# AST2003.net
KiCad netlist of a schematic drawn in EAGLE
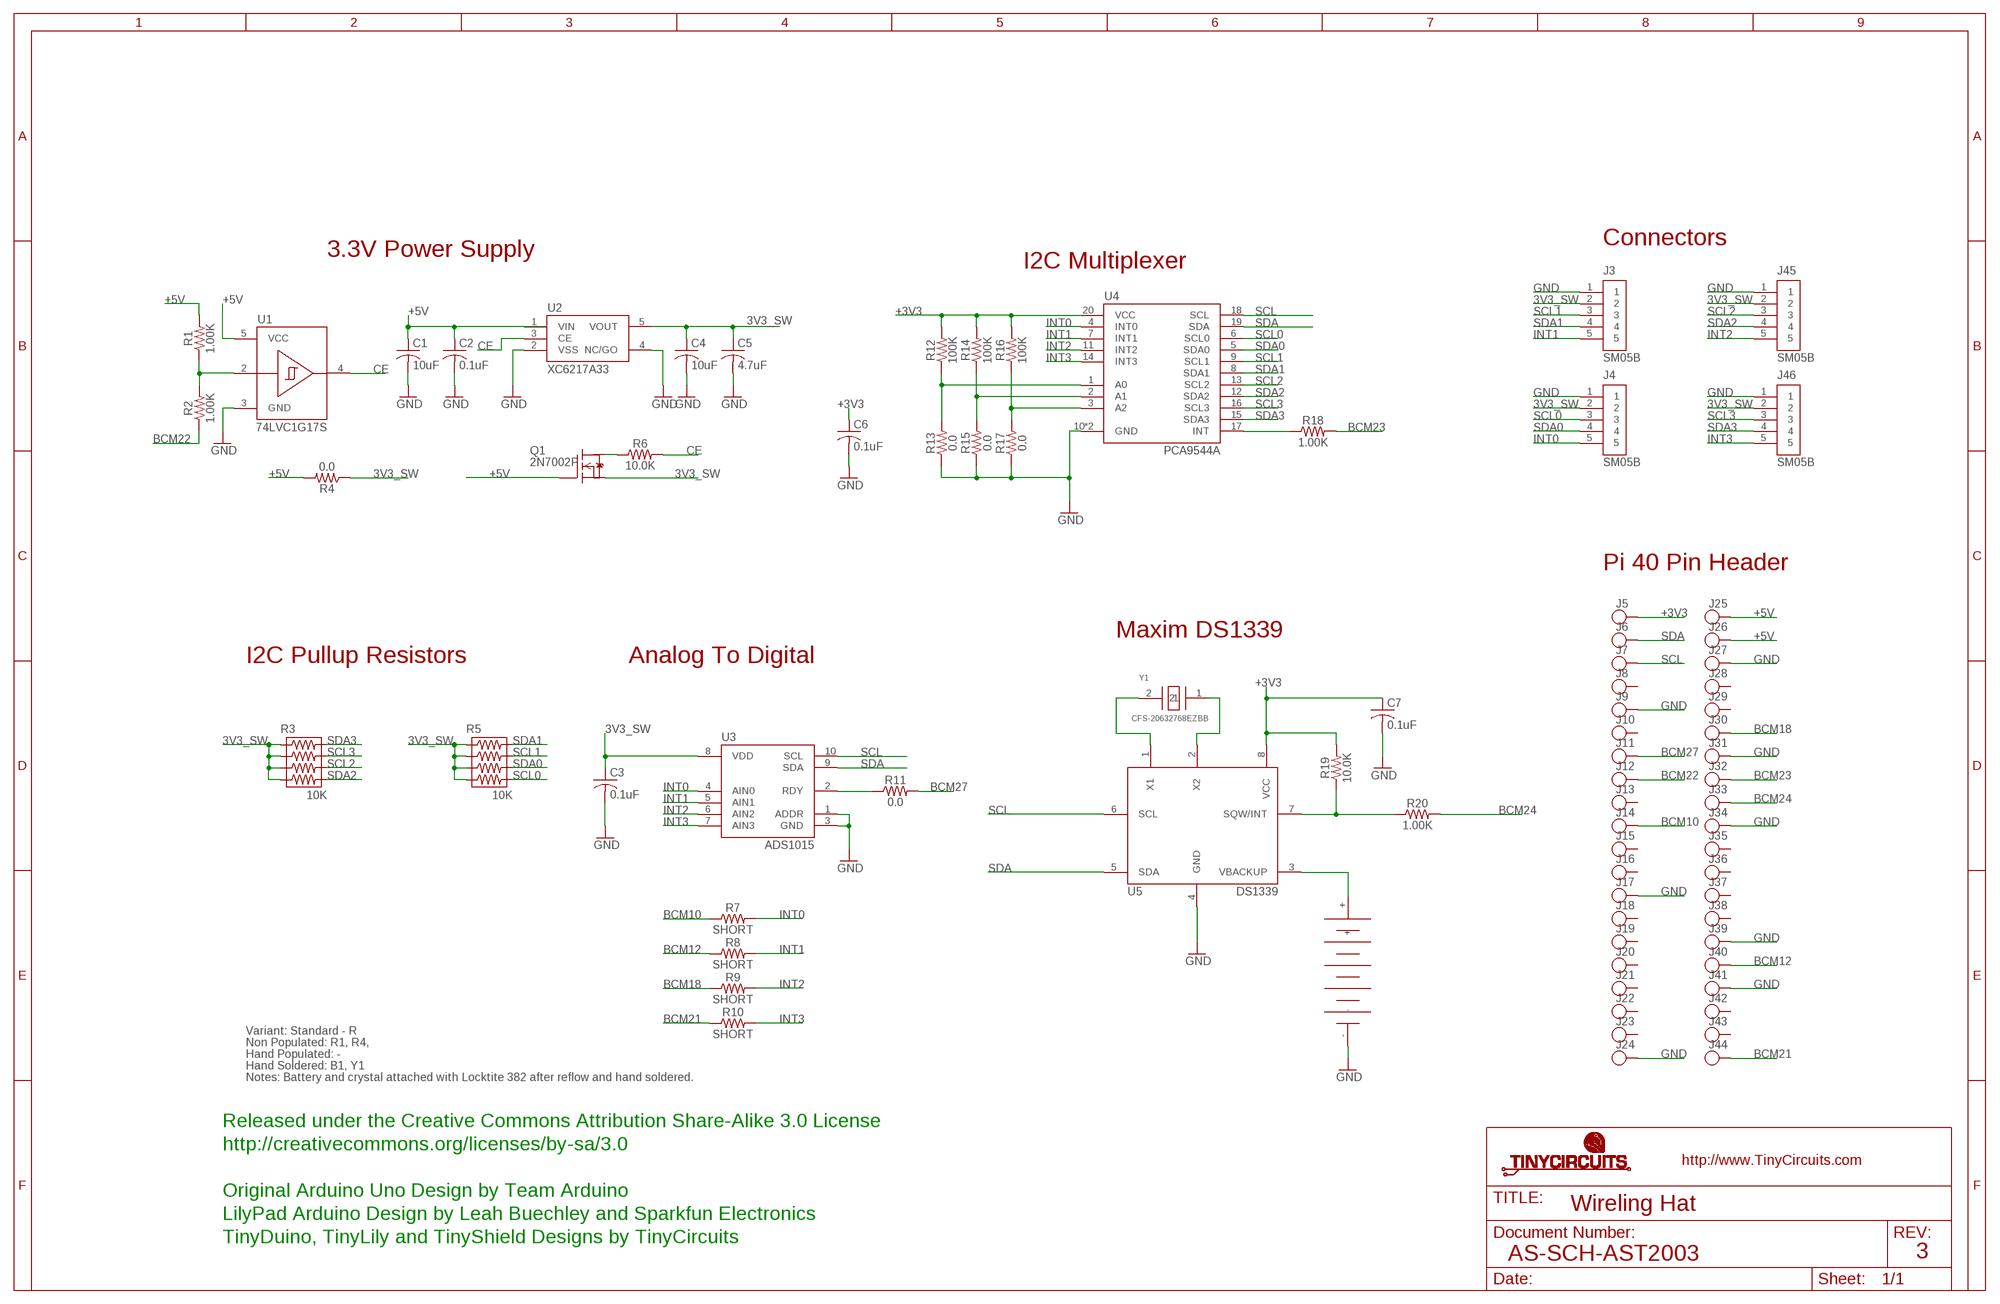
[diagram p0: schematic, sheet 1]

(export (version "E")
  (design (tool "Eeschema 10.0.6"))
  (components
    (comp (ref "B1")
      (value "ML-920S/DN")
      (footprint "eagle-import:ML-920S_DN")
      (fields (field (name "PARTNO") "AS-ITM-00182"))
      (libsource (lib "eagle-import") (part "AS-ITM-00182"))
    )
    (comp (ref "C1")
      (value "10uF")
      (footprint "eagle-import:C0603")
      (fields (field (name "PARTNO") "AS-ITM-00002") (field (name "PARTNO_1") "AS-ITM-00002"))
      (libsource (lib "eagle-import") (part "AS-ITM-00002"))
    )
    (comp (ref "C2")
      (value "0.1uF")
      (footprint "eagle-import:C0402")
      (fields (field (name "PARTNO") "AS-ITM-00008") (field (name "PARTNO_1") "AS-ITM-00008"))
      (libsource (lib "eagle-import") (part "AS-ITM-00008"))
    )
    (comp (ref "C3")
      (value "0.1uF")
      (footprint "eagle-import:C0402")
      (fields (field (name "PARTNO") "AS-ITM-00008"))
      (libsource (lib "eagle-import") (part "AS-ITM-00008"))
    )
    (comp (ref "C4")
      (value "10uF")
      (footprint "eagle-import:C0603")
      (fields (field (name "PARTNO") "AS-ITM-00002") (field (name "PARTNO_1") "AS-ITM-00002"))
      (libsource (lib "eagle-import") (part "AS-ITM-00002"))
    )
    (comp (ref "C5")
      (value "4.7uF")
      (footprint "eagle-import:C0402")
      (fields (field (name "PARTNO") "AS-ITM-00242") (field (name "PARTNO_1") "AS-ITM-00242"))
      (libsource (lib "eagle-import") (part "AS-ITM-00242"))
    )
    (comp (ref "C6")
      (value "0.1uF")
      (footprint "eagle-import:C0402")
      (fields (field (name "PARTNO") "AS-ITM-00008") (field (name "PARTNO_1") "AS-ITM-00008"))
      (libsource (lib "eagle-import") (part "AS-ITM-00008"))
    )
    (comp (ref "C7")
      (value "0.1uF")
      (footprint "eagle-import:C0402")
      (fields (field (name "PARTNO") "AS-ITM-00008"))
      (libsource (lib "eagle-import") (part "AS-ITM-00008"))
    )
    (comp (ref "J3")
      (value "SM05B")
      (footprint "eagle-import:JST_SH_5X1")
      (fields (field (name "PARTNO") "AS-ITM-00340"))
      (libsource (lib "eagle-import") (part "AS-ITM-00340"))
    )
    (comp (ref "J4")
      (value "SM05B")
      (footprint "eagle-import:JST_SH_5X1")
      (fields (field (name "PARTNO") "AS-ITM-00340"))
      (libsource (lib "eagle-import") (part "AS-ITM-00340"))
    )
    (comp (ref "J5")
      (value "PIN_1X.1\"1")
      (footprint "eagle-import:1X.1__2")
      (libsource (lib "eagle-import") (part "PIN_1X.1{dblquote}1"))
    )
    (comp (ref "J6")
      (value "PIN_1X.1\"1")
      (footprint "eagle-import:1X.1__2")
      (libsource (lib "eagle-import") (part "PIN_1X.1{dblquote}1"))
    )
    (comp (ref "J7")
      (value "PIN_1X.1\"1")
      (footprint "eagle-import:1X.1__2")
      (libsource (lib "eagle-import") (part "PIN_1X.1{dblquote}1"))
    )
    (comp (ref "J8")
      (value "PIN_1X.1\"1")
      (footprint "eagle-import:1X.1__2")
      (libsource (lib "eagle-import") (part "PIN_1X.1{dblquote}1"))
    )
    (comp (ref "J9")
      (value "PIN_1X.1\"1")
      (footprint "eagle-import:1X.1__2")
      (libsource (lib "eagle-import") (part "PIN_1X.1{dblquote}1"))
    )
    (comp (ref "J10")
      (value "PIN_1X.1\"1")
      (footprint "eagle-import:1X.1__2")
      (libsource (lib "eagle-import") (part "PIN_1X.1{dblquote}1"))
    )
    (comp (ref "J11")
      (value "PIN_1X.1\"1")
      (footprint "eagle-import:1X.1__2")
      (libsource (lib "eagle-import") (part "PIN_1X.1{dblquote}1"))
    )
    (comp (ref "J12")
      (value "PIN_1X.1\"1")
      (footprint "eagle-import:1X.1__2")
      (libsource (lib "eagle-import") (part "PIN_1X.1{dblquote}1"))
    )
    (comp (ref "J13")
      (value "PIN_1X.1\"1")
      (footprint "eagle-import:1X.1__2")
      (libsource (lib "eagle-import") (part "PIN_1X.1{dblquote}1"))
    )
    (comp (ref "J14")
      (value "PIN_1X.1\"1")
      (footprint "eagle-import:1X.1__2")
      (libsource (lib "eagle-import") (part "PIN_1X.1{dblquote}1"))
    )
    (comp (ref "J15")
      (value "PIN_1X.1\"1")
      (footprint "eagle-import:1X.1__2")
      (libsource (lib "eagle-import") (part "PIN_1X.1{dblquote}1"))
    )
    (comp (ref "J16")
      (value "PIN_1X.1\"1")
      (footprint "eagle-import:1X.1__2")
      (libsource (lib "eagle-import") (part "PIN_1X.1{dblquote}1"))
    )
    (comp (ref "J17")
      (value "PIN_1X.1\"1")
      (footprint "eagle-import:1X.1__2")
      (libsource (lib "eagle-import") (part "PIN_1X.1{dblquote}1"))
    )
    (comp (ref "J18")
      (value "PIN_1X.1\"1")
      (footprint "eagle-import:1X.1__2")
      (libsource (lib "eagle-import") (part "PIN_1X.1{dblquote}1"))
    )
    (comp (ref "J19")
      (value "PIN_1X.1\"1")
      (footprint "eagle-import:1X.1__2")
      (libsource (lib "eagle-import") (part "PIN_1X.1{dblquote}1"))
    )
    (comp (ref "J20")
      (value "PIN_1X.1\"1")
      (footprint "eagle-import:1X.1__2")
      (libsource (lib "eagle-import") (part "PIN_1X.1{dblquote}1"))
    )
    (comp (ref "J21")
      (value "PIN_1X.1\"1")
      (footprint "eagle-import:1X.1__2")
      (libsource (lib "eagle-import") (part "PIN_1X.1{dblquote}1"))
    )
    (comp (ref "J22")
      (value "PIN_1X.1\"1")
      (footprint "eagle-import:1X.1__2")
      (libsource (lib "eagle-import") (part "PIN_1X.1{dblquote}1"))
    )
    (comp (ref "J23")
      (value "PIN_1X.1\"1")
      (footprint "eagle-import:1X.1__2")
      (libsource (lib "eagle-import") (part "PIN_1X.1{dblquote}1"))
    )
    (comp (ref "J24")
      (value "PIN_1X.1\"1")
      (footprint "eagle-import:1X.1__2")
      (libsource (lib "eagle-import") (part "PIN_1X.1{dblquote}1"))
    )
    (comp (ref "J25")
      (value "PIN_1X.1\"1")
      (footprint "eagle-import:1X.1__2")
      (libsource (lib "eagle-import") (part "PIN_1X.1{dblquote}1"))
    )
    (comp (ref "J26")
      (value "PIN_1X.1\"1")
      (footprint "eagle-import:1X.1__2")
      (libsource (lib "eagle-import") (part "PIN_1X.1{dblquote}1"))
    )
    (comp (ref "J27")
      (value "PIN_1X.1\"1")
      (footprint "eagle-import:1X.1__2")
      (libsource (lib "eagle-import") (part "PIN_1X.1{dblquote}1"))
    )
    (comp (ref "J28")
      (value "PIN_1X.1\"1")
      (footprint "eagle-import:1X.1__2")
      (libsource (lib "eagle-import") (part "PIN_1X.1{dblquote}1"))
    )
    (comp (ref "J29")
      (value "PIN_1X.1\"1")
      (footprint "eagle-import:1X.1__2")
      (libsource (lib "eagle-import") (part "PIN_1X.1{dblquote}1"))
    )
    (comp (ref "J30")
      (value "PIN_1X.1\"1")
      (footprint "eagle-import:1X.1__2")
      (libsource (lib "eagle-import") (part "PIN_1X.1{dblquote}1"))
    )
    (comp (ref "J31")
      (value "PIN_1X.1\"1")
      (footprint "eagle-import:1X.1__2")
      (libsource (lib "eagle-import") (part "PIN_1X.1{dblquote}1"))
    )
    (comp (ref "J32")
      (value "PIN_1X.1\"1")
      (footprint "eagle-import:1X.1__2")
      (libsource (lib "eagle-import") (part "PIN_1X.1{dblquote}1"))
    )
    (comp (ref "J33")
      (value "PIN_1X.1\"1")
      (footprint "eagle-import:1X.1__2")
      (libsource (lib "eagle-import") (part "PIN_1X.1{dblquote}1"))
    )
    (comp (ref "J34")
      (value "PIN_1X.1\"1")
      (footprint "eagle-import:1X.1__2")
      (libsource (lib "eagle-import") (part "PIN_1X.1{dblquote}1"))
    )
    (comp (ref "J35")
      (value "PIN_1X.1\"1")
      (footprint "eagle-import:1X.1__2")
      (libsource (lib "eagle-import") (part "PIN_1X.1{dblquote}1"))
    )
    (comp (ref "J36")
      (value "PIN_1X.1\"1")
      (footprint "eagle-import:1X.1__2")
      (libsource (lib "eagle-import") (part "PIN_1X.1{dblquote}1"))
    )
    (comp (ref "J37")
      (value "PIN_1X.1\"1")
      (footprint "eagle-import:1X.1__2")
      (libsource (lib "eagle-import") (part "PIN_1X.1{dblquote}1"))
    )
    (comp (ref "J38")
      (value "PIN_1X.1\"1")
      (footprint "eagle-import:1X.1__2")
      (libsource (lib "eagle-import") (part "PIN_1X.1{dblquote}1"))
    )
    (comp (ref "J39")
      (value "PIN_1X.1\"1")
      (footprint "eagle-import:1X.1__2")
      (libsource (lib "eagle-import") (part "PIN_1X.1{dblquote}1"))
    )
    (comp (ref "J40")
      (value "PIN_1X.1\"1")
      (footprint "eagle-import:1X.1__2")
      (libsource (lib "eagle-import") (part "PIN_1X.1{dblquote}1"))
    )
    (comp (ref "J41")
      (value "PIN_1X.1\"1")
      (footprint "eagle-import:1X.1__2")
      (libsource (lib "eagle-import") (part "PIN_1X.1{dblquote}1"))
    )
    (comp (ref "J42")
      (value "PIN_1X.1\"1")
      (footprint "eagle-import:1X.1__2")
      (libsource (lib "eagle-import") (part "PIN_1X.1{dblquote}1"))
    )
    (comp (ref "J43")
      (value "PIN_1X.1\"1")
      (footprint "eagle-import:1X.1__2")
      (libsource (lib "eagle-import") (part "PIN_1X.1{dblquote}1"))
    )
    (comp (ref "J44")
      (value "PIN_1X.1\"1")
      (footprint "eagle-import:1X.1__2")
      (libsource (lib "eagle-import") (part "PIN_1X.1{dblquote}1"))
    )
    (comp (ref "J45")
      (value "SM05B")
      (footprint "eagle-import:JST_SH_5X1")
      (fields (field (name "PARTNO") "AS-ITM-00340"))
      (libsource (lib "eagle-import") (part "AS-ITM-00340"))
    )
    (comp (ref "J46")
      (value "SM05B")
      (footprint "eagle-import:JST_SH_5X1")
      (fields (field (name "PARTNO") "AS-ITM-00340"))
      (libsource (lib "eagle-import") (part "AS-ITM-00340"))
    )
    (comp (ref "Q1")
      (value "2N7002P")
      (footprint "eagle-import:SOT-416")
      (fields (field (name "PARTNO") "AS-ITM-00110") (field (name "PARTNO_1") "AS-ITM-00110"))
      (libsource (lib "eagle-import") (part "AS-ITM-00110"))
    )
    (comp (ref "R1")
      (value "1.00K")
      (footprint "eagle-import:0402")
      (fields (field (name "PARTNO") "AS-ITM-00003") (field (name "PARTNO_1") "AS-ITM-00003"))
      (libsource (lib "eagle-import") (part "AS-ITM-00003"))
    )
    (comp (ref "R2")
      (value "1.00K")
      (footprint "eagle-import:0402")
      (fields (field (name "PARTNO") "AS-ITM-00003") (field (name "PARTNO_1") "AS-ITM-00003"))
      (libsource (lib "eagle-import") (part "AS-ITM-00003"))
    )
    (comp (ref "R3")
      (value "10K")
      (footprint "eagle-import:0402RPACK")
      (fields (field (name "PARTNO") "AS-ITM-00520") (field (name "PARTNO_1") "AS-ITM-00520"))
      (libsource (lib "eagle-import") (part "AS-ITM-00520"))
    )
    (comp (ref "R4")
      (value "0.0")
      (footprint "eagle-import:0402")
      (fields (field (name "PARTNO") "AS-ITM-00076") (field (name "PARTNO_1") "AS-ITM-00076"))
      (libsource (lib "eagle-import") (part "AS-ITM-00076"))
    )
    (comp (ref "R5")
      (value "10K")
      (footprint "eagle-import:0402RPACK")
      (fields (field (name "PARTNO") "AS-ITM-00520") (field (name "PARTNO_1") "AS-ITM-00520"))
      (libsource (lib "eagle-import") (part "AS-ITM-00520"))
    )
    (comp (ref "R6")
      (value "10.0K")
      (footprint "eagle-import:0402")
      (fields (field (name "PARTNO") "AS-ITM-00032") (field (name "PARTNO_1") "AS-ITM-00032"))
      (libsource (lib "eagle-import") (part "AS-ITM-00032"))
    )
    (comp (ref "R7")
      (value "SHORT")
      (footprint "eagle-import:0402_SHORT")
      (fields (field (name "PARTNO") "AS-ITM-00076"))
      (libsource (lib "eagle-import") (part "AS-ITM-000760402_SHORT"))
    )
    (comp (ref "R8")
      (value "SHORT")
      (footprint "eagle-import:0402_SHORT")
      (fields (field (name "PARTNO") "AS-ITM-00076"))
      (libsource (lib "eagle-import") (part "AS-ITM-000760402_SHORT"))
    )
    (comp (ref "R9")
      (value "SHORT")
      (footprint "eagle-import:0402_SHORT")
      (fields (field (name "PARTNO") "AS-ITM-00076"))
      (libsource (lib "eagle-import") (part "AS-ITM-000760402_SHORT"))
    )
    (comp (ref "R10")
      (value "SHORT")
      (footprint "eagle-import:0402_SHORT")
      (fields (field (name "PARTNO") "AS-ITM-00076"))
      (libsource (lib "eagle-import") (part "AS-ITM-000760402_SHORT"))
    )
    (comp (ref "R11")
      (value "0.0")
      (footprint "eagle-import:0402")
      (fields (field (name "PARTNO") "AS-ITM-00076"))
      (libsource (lib "eagle-import") (part "AS-ITM-00076"))
    )
    (comp (ref "R12")
      (value "100K")
      (footprint "eagle-import:0402")
      (fields (field (name "PARTNO") "AS-ITM-00004") (field (name "PARTNO_1") "AS-ITM-00004"))
      (libsource (lib "eagle-import") (part "AS-ITM-00004"))
    )
    (comp (ref "R13")
      (value "0.0")
      (footprint "eagle-import:0402")
      (fields (field (name "PARTNO") "AS-ITM-00076") (field (name "PARTNO_1") "AS-ITM-00076"))
      (libsource (lib "eagle-import") (part "AS-ITM-00076"))
    )
    (comp (ref "R14")
      (value "100K")
      (footprint "eagle-import:0402")
      (fields (field (name "PARTNO") "AS-ITM-00004") (field (name "PARTNO_1") "AS-ITM-00004"))
      (libsource (lib "eagle-import") (part "AS-ITM-00004"))
    )
    (comp (ref "R15")
      (value "0.0")
      (footprint "eagle-import:0402")
      (fields (field (name "PARTNO") "AS-ITM-00076") (field (name "PARTNO_1") "AS-ITM-00076"))
      (libsource (lib "eagle-import") (part "AS-ITM-00076"))
    )
    (comp (ref "R16")
      (value "100K")
      (footprint "eagle-import:0402")
      (fields (field (name "PARTNO") "AS-ITM-00004") (field (name "PARTNO_1") "AS-ITM-00004"))
      (libsource (lib "eagle-import") (part "AS-ITM-00004"))
    )
    (comp (ref "R17")
      (value "0.0")
      (footprint "eagle-import:0402")
      (fields (field (name "PARTNO") "AS-ITM-00076") (field (name "PARTNO_1") "AS-ITM-00076"))
      (libsource (lib "eagle-import") (part "AS-ITM-00076"))
    )
    (comp (ref "R18")
      (value "1.00K")
      (footprint "eagle-import:0402")
      (fields (field (name "PARTNO") "AS-ITM-00003"))
      (libsource (lib "eagle-import") (part "AS-ITM-00003"))
    )
    (comp (ref "R19")
      (value "10.0K")
      (footprint "eagle-import:0402")
      (fields (field (name "PARTNO") "AS-ITM-00032") (field (name "PARTNO_1") "AS-ITM-00032"))
      (libsource (lib "eagle-import") (part "AS-ITM-00032"))
    )
    (comp (ref "R20")
      (value "1.00K")
      (footprint "eagle-import:0402")
      (fields (field (name "PARTNO") "AS-ITM-00003") (field (name "PARTNO_1") "AS-ITM-00003"))
      (libsource (lib "eagle-import") (part "AS-ITM-00003"))
    )
    (comp (ref "U1")
      (value "74LVC1G17S")
      (footprint "eagle-import:SOT-353")
      (fields (field (name "PARTNO") "AS-ITM-00382"))
      (libsource (lib "eagle-import") (part "AS-ITM-00382"))
    )
    (comp (ref "U2")
      (value "XC6217A33")
      (footprint "eagle-import:SOT-25")
      (fields (field (name "PARTNO") "AS-ITM-00249") (field (name "PARTNO_1") "AS-ITM-00249"))
      (libsource (lib "eagle-import") (part "AS-ITM-00249"))
    )
    (comp (ref "U3")
      (value "ADS1015")
      (footprint "eagle-import:R-PQFP-N10")
      (fields (field (name "PARTNO") "AS-ITM-00383"))
      (libsource (lib "eagle-import") (part "AS-ITM-00383"))
    )
    (comp (ref "U4")
      (value "PCA9544A")
      (footprint "eagle-import:VQFN-20_4.5X3.5")
      (fields (field (name "PARTNO") "AS-ITM-00342"))
      (libsource (lib "eagle-import") (part "AS-ITM-00342"))
    )
    (comp (ref "U5")
      (value "DS1339")
      (footprint "eagle-import:8-USOP")
      (fields (field (name "PARTNO") "AS-ITM-00181"))
      (libsource (lib "eagle-import") (part "AS-ITM-00181"))
    )
    (comp (ref "Y1")
      (value "CFS-20632768EZBB")
      (footprint "eagle-import:CRYSTAL_1.9MM_TH")
      (fields (field (name "PARTNO") "AS-ITM-00348"))
      (libsource (lib "eagle-import") (part "AS-ITM-00348"))
    )
  )
  (nets
    (net (code "1") (name "/+3V3") (class "Default")
      (node (ref "C6") (pin "1") (pinfunction "1_1") (pintype "passive"))
      (node (ref "C7") (pin "1") (pinfunction "1_1") (pintype "passive"))
      (node (ref "J5") (pin "1") (pinfunction "1_1") (pintype "bidirectional"))
      (node (ref "R12") (pin "2") (pinfunction "2_2") (pintype "passive"))
      (node (ref "R14") (pin "2") (pinfunction "2_2") (pintype "passive"))
      (node (ref "R16") (pin "2") (pinfunction "2_2") (pintype "passive"))
      (node (ref "R19") (pin "2") (pinfunction "2_2") (pintype "passive"))
      (node (ref "U4") (pin "20") (pinfunction "VCC_20") (pintype "bidirectional"))
      (node (ref "U5") (pin "8") (pinfunction "VCC_8") (pintype "bidirectional"))
    )
    (net (code "2") (name "/+5V") (class "Default")
      (node (ref "C1") (pin "1") (pinfunction "1_1") (pintype "passive"))
      (node (ref "C2") (pin "1") (pinfunction "1_1") (pintype "passive"))
      (node (ref "J25") (pin "1") (pinfunction "1_1") (pintype "bidirectional"))
      (node (ref "J26") (pin "1") (pinfunction "1_1") (pintype "bidirectional"))
      (node (ref "Q1") (pin "1") (pinfunction "G_1") (pintype "passive"))
      (node (ref "R1") (pin "2") (pinfunction "2_2") (pintype "passive"))
      (node (ref "R4") (pin "2") (pinfunction "2_2") (pintype "passive"))
      (node (ref "U1") (pin "5") (pinfunction "VCC_5") (pintype "bidirectional"))
      (node (ref "U2") (pin "1") (pinfunction "VIN_1") (pintype "bidirectional"))
    )
    (net (code "3") (name "/3V3_SW") (class "Default")
      (node (ref "C3") (pin "1") (pinfunction "1_1") (pintype "passive"))
      (node (ref "C4") (pin "1") (pinfunction "1_1") (pintype "passive"))
      (node (ref "C5") (pin "1") (pinfunction "1_1") (pintype "passive"))
      (node (ref "J3") (pin "2") (pinfunction "2_2") (pintype "bidirectional"))
      (node (ref "J4") (pin "2") (pinfunction "2_2") (pintype "bidirectional"))
      (node (ref "J45") (pin "2") (pinfunction "2_2") (pintype "bidirectional"))
      (node (ref "J46") (pin "2") (pinfunction "2_2") (pintype "bidirectional"))
      (node (ref "Q1") (pin "2") (pinfunction "S_2") (pintype "passive"))
      (node (ref "R3") (pin "1") (pinfunction "1_1") (pintype "passive"))
      (node (ref "R3") (pin "3") (pinfunction "3_3") (pintype "passive"))
      (node (ref "R3") (pin "5") (pinfunction "5_5") (pintype "passive"))
      (node (ref "R3") (pin "7") (pinfunction "7_7") (pintype "passive"))
      (node (ref "R4") (pin "1") (pinfunction "1_1") (pintype "passive"))
      (node (ref "R5") (pin "1") (pinfunction "1_1") (pintype "passive"))
      (node (ref "R5") (pin "3") (pinfunction "3_3") (pintype "passive"))
      (node (ref "R5") (pin "5") (pinfunction "5_5") (pintype "passive"))
      (node (ref "R5") (pin "7") (pinfunction "7_7") (pintype "passive"))
      (node (ref "U2") (pin "5") (pinfunction "VOUT_5") (pintype "bidirectional"))
      (node (ref "U3") (pin "8") (pinfunction "VDD_8") (pintype "bidirectional"))
    )
    (net (code "4") (name "/BCM10") (class "Default")
      (node (ref "J14") (pin "1") (pinfunction "1_1") (pintype "bidirectional"))
      (node (ref "R7") (pin "1") (pinfunction "1_1") (pintype "passive"))
    )
    (net (code "5") (name "/BCM12") (class "Default")
      (node (ref "J40") (pin "1") (pinfunction "1_1") (pintype "bidirectional"))
      (node (ref "R8") (pin "1") (pinfunction "1_1") (pintype "passive"))
    )
    (net (code "6") (name "/BCM18") (class "Default")
      (node (ref "J30") (pin "1") (pinfunction "1_1") (pintype "bidirectional"))
      (node (ref "R9") (pin "1") (pinfunction "1_1") (pintype "passive"))
    )
    (net (code "7") (name "/BCM21") (class "Default")
      (node (ref "J44") (pin "1") (pinfunction "1_1") (pintype "bidirectional"))
      (node (ref "R10") (pin "1") (pinfunction "1_1") (pintype "passive"))
    )
    (net (code "8") (name "/BCM22") (class "Default")
      (node (ref "J12") (pin "1") (pinfunction "1_1") (pintype "bidirectional"))
      (node (ref "R2") (pin "1") (pinfunction "1_1") (pintype "passive"))
    )
    (net (code "9") (name "/BCM23") (class "Default")
      (node (ref "J32") (pin "1") (pinfunction "1_1") (pintype "bidirectional"))
      (node (ref "R18") (pin "2") (pinfunction "2_2") (pintype "passive"))
    )
    (net (code "10") (name "/BCM24") (class "Default")
      (node (ref "J33") (pin "1") (pinfunction "1_1") (pintype "bidirectional"))
      (node (ref "R20") (pin "2") (pinfunction "2_2") (pintype "passive"))
    )
    (net (code "11") (name "/BCM27") (class "Default")
      (node (ref "J11") (pin "1") (pinfunction "1_1") (pintype "bidirectional"))
      (node (ref "R11") (pin "2") (pinfunction "2_2") (pintype "passive"))
    )
    (net (code "12") (name "/CE") (class "Default")
      (node (ref "R6") (pin "2") (pinfunction "2_2") (pintype "passive"))
      (node (ref "U1") (pin "4") (pinfunction "Y_4") (pintype "bidirectional"))
      (node (ref "U2") (pin "3") (pinfunction "CE_3") (pintype "bidirectional"))
    )
    (net (code "13") (name "/INT0") (class "Default")
      (node (ref "J4") (pin "5") (pinfunction "5_5") (pintype "bidirectional"))
      (node (ref "R7") (pin "2") (pinfunction "2_2") (pintype "passive"))
      (node (ref "U3") (pin "4") (pinfunction "AIN0_4") (pintype "bidirectional"))
      (node (ref "U4") (pin "4") (pinfunction "INT0_4") (pintype "bidirectional"))
    )
    (net (code "14") (name "/INT1") (class "Default")
      (node (ref "J3") (pin "5") (pinfunction "5_5") (pintype "bidirectional"))
      (node (ref "R8") (pin "2") (pinfunction "2_2") (pintype "passive"))
      (node (ref "U3") (pin "5") (pinfunction "AIN1_5") (pintype "bidirectional"))
      (node (ref "U4") (pin "7") (pinfunction "INT1_7") (pintype "bidirectional"))
    )
    (net (code "15") (name "/INT2") (class "Default")
      (node (ref "J45") (pin "5") (pinfunction "5_5") (pintype "bidirectional"))
      (node (ref "R9") (pin "2") (pinfunction "2_2") (pintype "passive"))
      (node (ref "U3") (pin "6") (pinfunction "AIN2_6") (pintype "bidirectional"))
      (node (ref "U4") (pin "11") (pinfunction "INT2_11") (pintype "bidirectional"))
    )
    (net (code "16") (name "/INT3") (class "Default")
      (node (ref "J46") (pin "5") (pinfunction "5_5") (pintype "bidirectional"))
      (node (ref "R10") (pin "2") (pinfunction "2_2") (pintype "passive"))
      (node (ref "U3") (pin "7") (pinfunction "AIN3_7") (pintype "bidirectional"))
      (node (ref "U4") (pin "14") (pinfunction "INT3_14") (pintype "bidirectional"))
    )
    (net (code "17") (name "/SCL") (class "Default")
      (node (ref "J7") (pin "1") (pinfunction "1_1") (pintype "bidirectional"))
      (node (ref "U3") (pin "10") (pinfunction "SCL_10") (pintype "bidirectional"))
      (node (ref "U4") (pin "18") (pinfunction "SCL_18") (pintype "bidirectional"))
      (node (ref "U5") (pin "6") (pinfunction "SCL_6") (pintype "bidirectional"))
    )
    (net (code "18") (name "/SCL0") (class "Default")
      (node (ref "J4") (pin "3") (pinfunction "3_3") (pintype "bidirectional"))
      (node (ref "R5") (pin "8") (pinfunction "8_8") (pintype "passive"))
      (node (ref "U4") (pin "6") (pinfunction "SCL0_6") (pintype "bidirectional"))
    )
    (net (code "19") (name "/SCL1") (class "Default")
      (node (ref "J3") (pin "3") (pinfunction "3_3") (pintype "bidirectional"))
      (node (ref "R5") (pin "4") (pinfunction "4_4") (pintype "passive"))
      (node (ref "U4") (pin "9") (pinfunction "SCL1_9") (pintype "bidirectional"))
    )
    (net (code "20") (name "/SCL2") (class "Default")
      (node (ref "J45") (pin "3") (pinfunction "3_3") (pintype "bidirectional"))
      (node (ref "R3") (pin "6") (pinfunction "6_6") (pintype "passive"))
      (node (ref "U4") (pin "13") (pinfunction "SCL2_13") (pintype "bidirectional"))
    )
    (net (code "21") (name "/SCL3") (class "Default")
      (node (ref "J46") (pin "3") (pinfunction "3_3") (pintype "bidirectional"))
      (node (ref "R3") (pin "4") (pinfunction "4_4") (pintype "passive"))
      (node (ref "U4") (pin "16") (pinfunction "SCL3_16") (pintype "bidirectional"))
    )
    (net (code "22") (name "/SDA") (class "Default")
      (node (ref "J6") (pin "1") (pinfunction "1_1") (pintype "bidirectional"))
      (node (ref "U3") (pin "9") (pinfunction "SDA_9") (pintype "bidirectional"))
      (node (ref "U4") (pin "19") (pinfunction "SDA_19") (pintype "bidirectional"))
      (node (ref "U5") (pin "5") (pinfunction "SDA_5") (pintype "bidirectional"))
    )
    (net (code "23") (name "/SDA0") (class "Default")
      (node (ref "J4") (pin "4") (pinfunction "4_4") (pintype "bidirectional"))
      (node (ref "R5") (pin "6") (pinfunction "6_6") (pintype "passive"))
      (node (ref "U4") (pin "5") (pinfunction "SDA0_5") (pintype "bidirectional"))
    )
    (net (code "24") (name "/SDA1") (class "Default")
      (node (ref "J3") (pin "4") (pinfunction "4_4") (pintype "bidirectional"))
      (node (ref "R5") (pin "2") (pinfunction "2_2") (pintype "passive"))
      (node (ref "U4") (pin "8") (pinfunction "SDA1_8") (pintype "bidirectional"))
    )
    (net (code "25") (name "/SDA2") (class "Default")
      (node (ref "J45") (pin "4") (pinfunction "4_4") (pintype "bidirectional"))
      (node (ref "R3") (pin "8") (pinfunction "8_8") (pintype "passive"))
      (node (ref "U4") (pin "12") (pinfunction "SDA2_12") (pintype "bidirectional"))
    )
    (net (code "26") (name "/SDA3") (class "Default")
      (node (ref "J46") (pin "4") (pinfunction "4_4") (pintype "bidirectional"))
      (node (ref "R3") (pin "2") (pinfunction "2_2") (pintype "passive"))
      (node (ref "U4") (pin "15") (pinfunction "SDA3_15") (pintype "bidirectional"))
    )
    (net (code "27") (name "GND") (class "Default")
      (node (ref "B1") (pin "-") (pinfunction "-_-") (pintype "bidirectional"))
      (node (ref "C1") (pin "2") (pinfunction "2_2") (pintype "passive"))
      (node (ref "C2") (pin "2") (pinfunction "2_2") (pintype "passive"))
      (node (ref "C3") (pin "2") (pinfunction "2_2") (pintype "passive"))
      (node (ref "C4") (pin "2") (pinfunction "2_2") (pintype "passive"))
      (node (ref "C5") (pin "2") (pinfunction "2_2") (pintype "passive"))
      (node (ref "C6") (pin "2") (pinfunction "2_2") (pintype "passive"))
      (node (ref "C7") (pin "2") (pinfunction "2_2") (pintype "passive"))
      (node (ref "J17") (pin "1") (pinfunction "1_1") (pintype "bidirectional"))
      (node (ref "J24") (pin "1") (pinfunction "1_1") (pintype "bidirectional"))
      (node (ref "J27") (pin "1") (pinfunction "1_1") (pintype "bidirectional"))
      (node (ref "J3") (pin "1") (pinfunction "1_1") (pintype "bidirectional"))
      (node (ref "J31") (pin "1") (pinfunction "1_1") (pintype "bidirectional"))
      (node (ref "J34") (pin "1") (pinfunction "1_1") (pintype "bidirectional"))
      (node (ref "J39") (pin "1") (pinfunction "1_1") (pintype "bidirectional"))
      (node (ref "J4") (pin "1") (pinfunction "1_1") (pintype "bidirectional"))
      (node (ref "J41") (pin "1") (pinfunction "1_1") (pintype "bidirectional"))
      (node (ref "J45") (pin "1") (pinfunction "1_1") (pintype "bidirectional"))
      (node (ref "J46") (pin "1") (pinfunction "1_1") (pintype "bidirectional"))
      (node (ref "J9") (pin "1") (pinfunction "1_1") (pintype "bidirectional"))
      (node (ref "R13") (pin "1") (pinfunction "1_1") (pintype "passive"))
      (node (ref "R15") (pin "1") (pinfunction "1_1") (pintype "passive"))
      (node (ref "R17") (pin "1") (pinfunction "1_1") (pintype "passive"))
      (node (ref "U1") (pin "3") (pinfunction "GND_3") (pintype "bidirectional"))
      (node (ref "U2") (pin "2") (pinfunction "VSS_2") (pintype "power_in"))
      (node (ref "U2") (pin "4") (pinfunction "NC/GO_4") (pintype "bidirectional"))
      (node (ref "U3") (pin "1") (pinfunction "ADDR_1") (pintype "bidirectional"))
      (node (ref "U3") (pin "3") (pinfunction "GND_3") (pintype "bidirectional"))
      (node (ref "U4") (pin "10") (pinfunction "GND_10") (pintype "bidirectional"))
      (node (ref "U4") (pin "PAD") (pinfunction "GND_PAD") (pintype "bidirectional"))
      (node (ref "U5") (pin "4") (pinfunction "GND_4") (pintype "bidirectional"))
    )
    (net (code "28") (name "Net-(Q1-D)") (class "Default")
      (node (ref "Q1") (pin "3") (pinfunction "D_3") (pintype "passive"))
      (node (ref "R6") (pin "1") (pinfunction "1_1") (pintype "passive"))
    )
    (net (code "29") (name "Net-(U1-A)") (class "Default")
      (node (ref "R1") (pin "1") (pinfunction "1_1") (pintype "passive"))
      (node (ref "R2") (pin "2") (pinfunction "2_2") (pintype "passive"))
      (node (ref "U1") (pin "2") (pinfunction "A_2") (pintype "bidirectional"))
    )
    (net (code "30") (name "Net-(U3-RDY)") (class "Default")
      (node (ref "R11") (pin "1") (pinfunction "1_1") (pintype "passive"))
      (node (ref "U3") (pin "2") (pinfunction "RDY_2") (pintype "bidirectional"))
    )
    (net (code "31") (name "Net-(U4-A0)") (class "Default")
      (node (ref "R12") (pin "1") (pinfunction "1_1") (pintype "passive"))
      (node (ref "R13") (pin "2") (pinfunction "2_2") (pintype "passive"))
      (node (ref "U4") (pin "1") (pinfunction "A0_1") (pintype "bidirectional"))
    )
    (net (code "32") (name "Net-(U4-A1)") (class "Default")
      (node (ref "R14") (pin "1") (pinfunction "1_1") (pintype "passive"))
      (node (ref "R15") (pin "2") (pinfunction "2_2") (pintype "passive"))
      (node (ref "U4") (pin "2") (pinfunction "A1_2") (pintype "bidirectional"))
    )
    (net (code "33") (name "Net-(U4-A2)") (class "Default")
      (node (ref "R16") (pin "1") (pinfunction "1_1") (pintype "passive"))
      (node (ref "R17") (pin "2") (pinfunction "2_2") (pintype "passive"))
      (node (ref "U4") (pin "3") (pinfunction "A2_3") (pintype "bidirectional"))
    )
    (net (code "34") (name "Net-(U4-INT)") (class "Default")
      (node (ref "R18") (pin "1") (pinfunction "1_1") (pintype "passive"))
      (node (ref "U4") (pin "17") (pinfunction "INT_17") (pintype "bidirectional"))
    )
    (net (code "35") (name "Net-(U5-SQW{slash}INT)") (class "Default")
      (node (ref "R19") (pin "1") (pinfunction "1_1") (pintype "passive"))
      (node (ref "R20") (pin "1") (pinfunction "1_1") (pintype "passive"))
      (node (ref "U5") (pin "7") (pinfunction "SQW/INT_7") (pintype "bidirectional"))
    )
    (net (code "36") (name "Net-(U5-VBACKUP)") (class "Default")
      (node (ref "B1") (pin "+") (pinfunction "+_+") (pintype "bidirectional"))
      (node (ref "U5") (pin "3") (pinfunction "VBACKUP_3") (pintype "bidirectional"))
    )
    (net (code "37") (name "Net-(U5-X1)") (class "Default")
      (node (ref "U5") (pin "1") (pinfunction "X1_1") (pintype "bidirectional"))
      (node (ref "Y1") (pin "2") (pinfunction "1_2") (pintype "bidirectional"))
    )
    (net (code "38") (name "Net-(U5-X2)") (class "Default")
      (node (ref "U5") (pin "2") (pinfunction "X2_2") (pintype "bidirectional"))
      (node (ref "Y1") (pin "1") (pinfunction "2_1") (pintype "bidirectional"))
    )
    (net (code "39") (name "unconnected-(J8-Pad1)") (class "Default")
      (node (ref "J8") (pin "1") (pinfunction "1_1") (pintype "bidirectional"))
    )
    (net (code "40") (name "unconnected-(J10-Pad1)") (class "Default")
      (node (ref "J10") (pin "1") (pinfunction "1_1") (pintype "bidirectional"))
    )
    (net (code "41") (name "unconnected-(J13-Pad1)") (class "Default")
      (node (ref "J13") (pin "1") (pinfunction "1_1") (pintype "bidirectional"))
    )
    (net (code "42") (name "unconnected-(J15-Pad1)") (class "Default")
      (node (ref "J15") (pin "1") (pinfunction "1_1") (pintype "bidirectional"))
    )
    (net (code "43") (name "unconnected-(J16-Pad1)") (class "Default")
      (node (ref "J16") (pin "1") (pinfunction "1_1") (pintype "bidirectional"))
    )
    (net (code "44") (name "unconnected-(J18-Pad1)") (class "Default")
      (node (ref "J18") (pin "1") (pinfunction "1_1") (pintype "bidirectional"))
    )
    (net (code "45") (name "unconnected-(J19-Pad1)") (class "Default")
      (node (ref "J19") (pin "1") (pinfunction "1_1") (pintype "bidirectional"))
    )
    (net (code "46") (name "unconnected-(J20-Pad1)") (class "Default")
      (node (ref "J20") (pin "1") (pinfunction "1_1") (pintype "bidirectional"))
    )
    (net (code "47") (name "unconnected-(J21-Pad1)") (class "Default")
      (node (ref "J21") (pin "1") (pinfunction "1_1") (pintype "bidirectional"))
    )
    (net (code "48") (name "unconnected-(J22-Pad1)") (class "Default")
      (node (ref "J22") (pin "1") (pinfunction "1_1") (pintype "bidirectional"))
    )
    (net (code "49") (name "unconnected-(J23-Pad1)") (class "Default")
      (node (ref "J23") (pin "1") (pinfunction "1_1") (pintype "bidirectional"))
    )
    (net (code "50") (name "unconnected-(J28-Pad1)") (class "Default")
      (node (ref "J28") (pin "1") (pinfunction "1_1") (pintype "bidirectional"))
    )
    (net (code "51") (name "unconnected-(J29-Pad1)") (class "Default")
      (node (ref "J29") (pin "1") (pinfunction "1_1") (pintype "bidirectional"))
    )
    (net (code "52") (name "unconnected-(J35-Pad1)") (class "Default")
      (node (ref "J35") (pin "1") (pinfunction "1_1") (pintype "bidirectional"))
    )
    (net (code "53") (name "unconnected-(J36-Pad1)") (class "Default")
      (node (ref "J36") (pin "1") (pinfunction "1_1") (pintype "bidirectional"))
    )
    (net (code "54") (name "unconnected-(J37-Pad1)") (class "Default")
      (node (ref "J37") (pin "1") (pinfunction "1_1") (pintype "bidirectional"))
    )
    (net (code "55") (name "unconnected-(J38-Pad1)") (class "Default")
      (node (ref "J38") (pin "1") (pinfunction "1_1") (pintype "bidirectional"))
    )
    (net (code "56") (name "unconnected-(J42-Pad1)") (class "Default")
      (node (ref "J42") (pin "1") (pinfunction "1_1") (pintype "bidirectional"))
    )
    (net (code "57") (name "unconnected-(J43-Pad1)") (class "Default")
      (node (ref "J43") (pin "1") (pinfunction "1_1") (pintype "bidirectional"))
    )
  )
)
